# Communications.net
KiCad netlist of a schematic drawn in Altium Designer
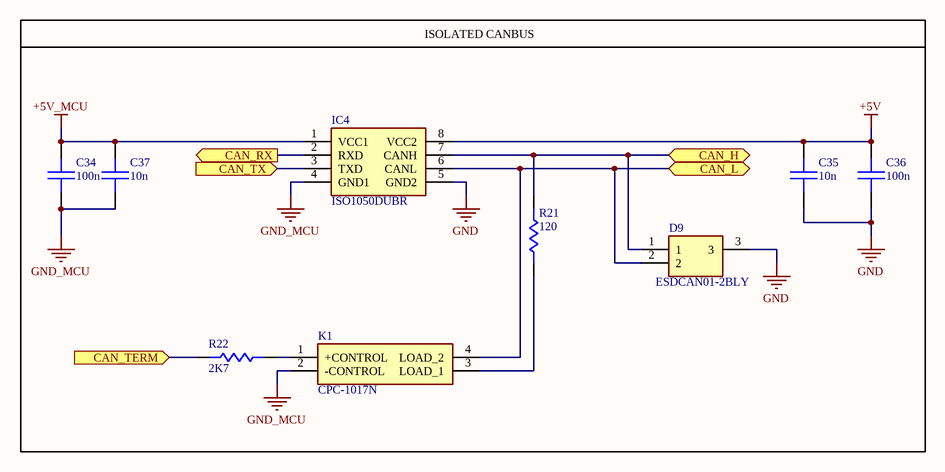
[diagram p0: Communications.SchDoc]

(export (version "E")
  (design (tool "Eeschema 10.0.6"))
  (components
    (comp (ref "C34")
      (value "100n")
      (footprint "C_0603")
      (description "SMD Chip Capacitor")
      (libsource (lib "My_Integrated_Lib") (part "CAP"))
    )
    (comp (ref "C35")
      (value "10n")
      (footprint "C_0603")
      (description "SMD Chip Capacitor")
      (libsource (lib "My_Integrated_Lib") (part "CAP"))
    )
    (comp (ref "C36")
      (value "100n")
      (footprint "C_0603")
      (description "SMD Chip Capacitor")
      (libsource (lib "My_Integrated_Lib") (part "CAP"))
    )
    (comp (ref "C37")
      (value "10n")
      (footprint "C_0603")
      (description "SMD Chip Capacitor")
      (libsource (lib "My_Integrated_Lib") (part "CAP"))
    )
    (comp (ref "D9")
      (value "ESDCAN01-2BLY")
      (footprint "SOT95P255X125-3N")
      (description "TVS Diode (Bi-directional)")
      (fields (field (name "MOUSER PART NUMBER") "511-ESDCAN01-2BLY"))
      (libsource (lib "My_Integrated_Lib") (part "ESDCAN01-2BLY"))
    )
    (comp (ref "IC4")
      (value "ISO1050DUBR")
      (footprint "SOP254P1040X485-8N")
      (description "Integrated Circuit")
      (fields (field (name "MOUSER PART NUMBER") "595-ISO1050DUBR"))
      (libsource (lib "My_Integrated_Lib") (part "ISO1050DUBR"))
    )
    (comp (ref "K1")
      (value "CPC-1017N")
      (footprint "SOP254P610X206-4N")
      (description "Relay or Contactor")
      (libsource (lib "My_Integrated_Lib") (part "CPC-1017N"))
    )
    (comp (ref "R21")
      (value "120")
      (footprint "R_0603")
      (description "SMD Chip Resistor")
      (libsource (lib "My_Integrated_Lib") (part "RES"))
    )
    (comp (ref "R22")
      (value "2K7")
      (footprint "R_0603")
      (description "SMD Chip Resistor")
      (libsource (lib "My_Integrated_Lib") (part "RES"))
    )
  )
  (nets
    (net (code "1") (name "+5V") (class "Default")
      (node (ref "C35") (pin "1") (pinfunction "1_1") (pintype "passive"))
      (node (ref "C36") (pin "1") (pinfunction "1_1") (pintype "passive"))
      (node (ref "IC4") (pin "8") (pinfunction "VCC2_8") (pintype "passive"))
    )
    (net (code "2") (name "+5V_MCU") (class "Default")
      (node (ref "C34") (pin "2") (pinfunction "2_2") (pintype "passive"))
      (node (ref "C37") (pin "1") (pinfunction "1_1") (pintype "passive"))
      (node (ref "IC4") (pin "1") (pinfunction "VCC1_1") (pintype "passive"))
    )
    (net (code "3") (name "/CAN_H") (class "Default")
      (node (ref "D9") (pin "1") (pinfunction "1_1") (pintype "passive"))
      (node (ref "IC4") (pin "7") (pinfunction "CANH_7") (pintype "passive"))
      (node (ref "R21") (pin "2") (pinfunction "2_2") (pintype "passive"))
    )
    (net (code "4") (name "/CAN_L") (class "Default")
      (node (ref "D9") (pin "2") (pinfunction "2_2") (pintype "passive"))
      (node (ref "IC4") (pin "6") (pinfunction "CANL_6") (pintype "passive"))
      (node (ref "K1") (pin "4") (pinfunction "LOAD_2_4") (pintype "passive"))
    )
    (net (code "5") (name "/CAN_RX") (class "Default")
      (node (ref "IC4") (pin "2") (pinfunction "RXD_2") (pintype "passive"))
    )
    (net (code "6") (name "/CAN_TERM") (class "Default")
      (node (ref "R22") (pin "2") (pinfunction "2_2") (pintype "passive"))
    )
    (net (code "7") (name "/CAN_TX") (class "Default")
      (node (ref "IC4") (pin "3") (pinfunction "TXD_3") (pintype "passive"))
    )
    (net (code "8") (name "GND") (class "Default")
      (node (ref "C35") (pin "2") (pinfunction "2_2") (pintype "passive"))
      (node (ref "C36") (pin "2") (pinfunction "2_2") (pintype "passive"))
      (node (ref "D9") (pin "3") (pinfunction "3_3") (pintype "passive"))
      (node (ref "IC4") (pin "5") (pinfunction "GND2_5") (pintype "passive"))
    )
    (net (code "9") (name "GND_MCU") (class "Default")
      (node (ref "C34") (pin "1") (pinfunction "1_1") (pintype "passive"))
      (node (ref "C37") (pin "2") (pinfunction "2_2") (pintype "passive"))
      (node (ref "IC4") (pin "4") (pinfunction "GND1_4") (pintype "passive"))
      (node (ref "K1") (pin "2") (pinfunction "-CONTROL_2") (pintype "passive"))
    )
    (net (code "10") (name "Net-(K1-+CONTROL)") (class "Default")
      (node (ref "K1") (pin "1") (pinfunction "+CONTROL_1") (pintype "passive"))
      (node (ref "R22") (pin "1") (pinfunction "1_1") (pintype "passive"))
    )
    (net (code "11") (name "Net-(K1-LOAD_1)") (class "Default")
      (node (ref "K1") (pin "3") (pinfunction "LOAD_1_3") (pintype "passive"))
      (node (ref "R21") (pin "1") (pinfunction "1_1") (pintype "passive"))
    )
  )
)
